# BLE_test.net
KiCad netlist of a schematic drawn in EAGLE
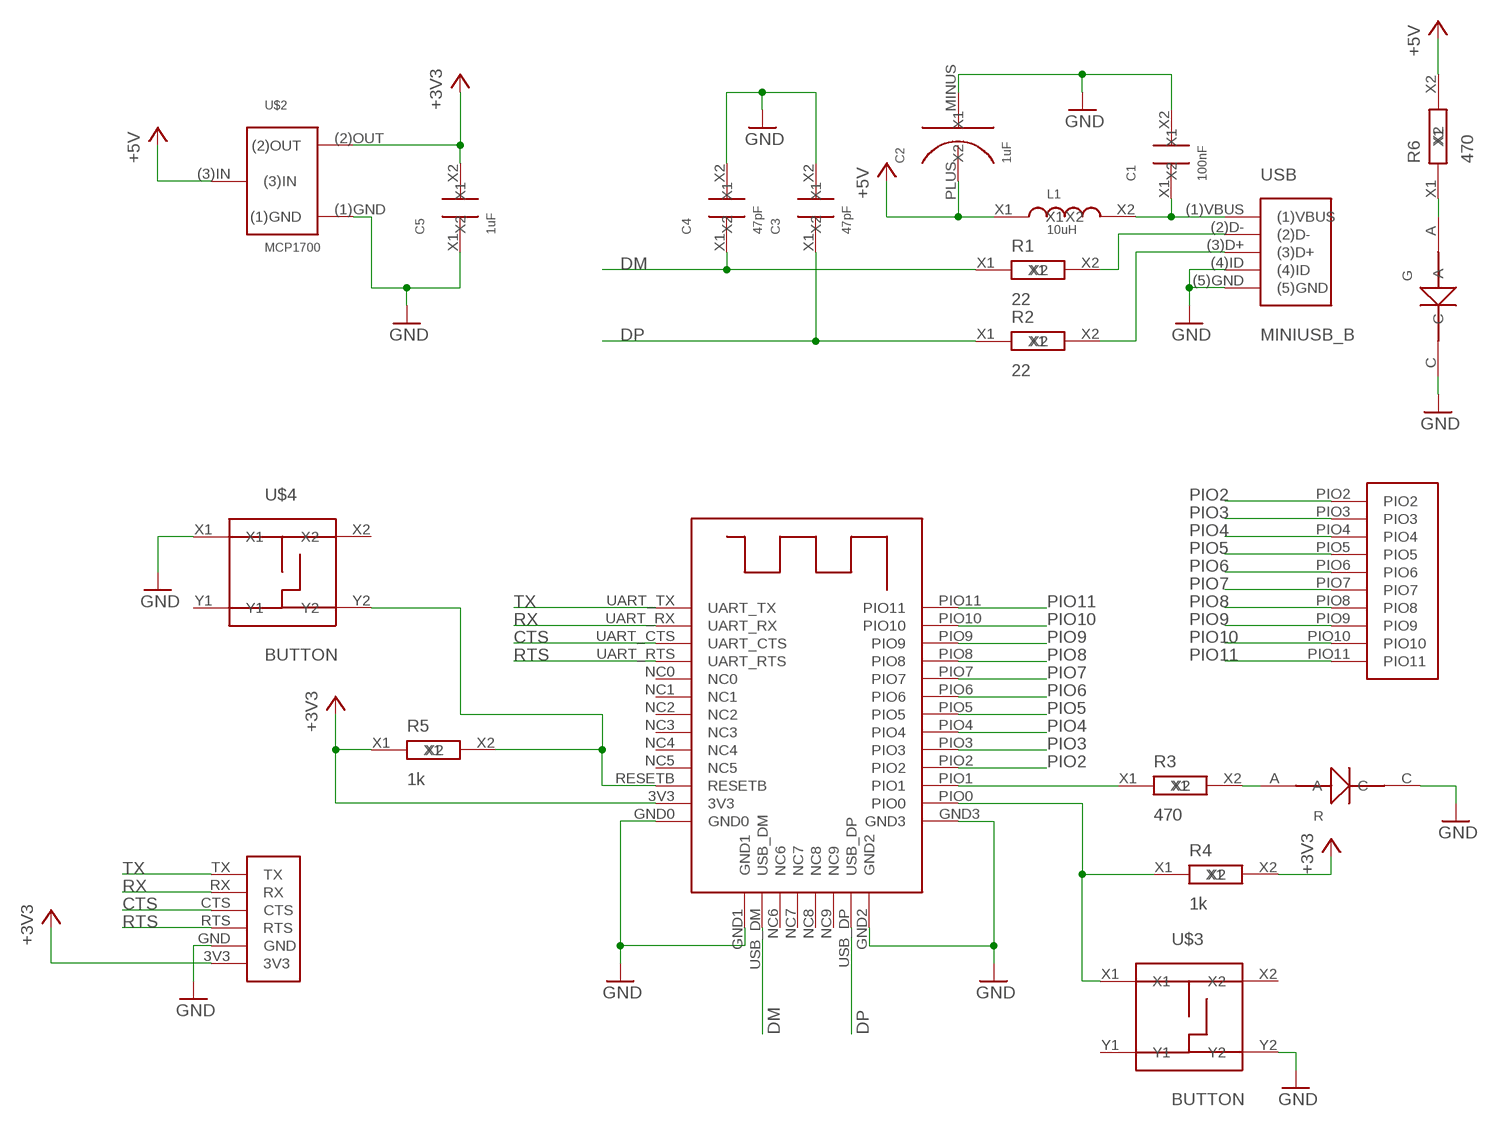
[diagram p0: schematic, sheet 1]

(export (version "E")
  (design (tool "Eeschema 10.0.6"))
  (components
    (comp (ref "C1")
      (value "100nF")
      (footprint "eagle-import:SMD_2.1X1.25")
      (libsource (lib "eagle-import") (part "C_SMD_2.1X1.25"))
    )
    (comp (ref "C2")
      (value "1uF")
      (footprint "eagle-import:C_SMD_TA_A")
      (libsource (lib "eagle-import") (part "C_SMD_TA_A"))
    )
    (comp (ref "C3")
      (value "47pF")
      (footprint "eagle-import:SMD_2.1X1.25")
      (libsource (lib "eagle-import") (part "C_SMD_2.1X1.25"))
    )
    (comp (ref "C4")
      (value "47pF")
      (footprint "eagle-import:SMD_2.1X1.25")
      (libsource (lib "eagle-import") (part "C_SMD_2.1X1.25"))
    )
    (comp (ref "C5")
      (value "1uF")
      (footprint "eagle-import:SMD_2.1X1.25")
      (libsource (lib "eagle-import") (part "C_SMD_2.1X1.25"))
    )
    (comp (ref "G")
      (value "LED0805")
      (footprint "eagle-import:SMD0805")
      (libsource (lib "eagle-import") (part "LED0805"))
    )
    (comp (ref "L1")
      (value "10uH")
      (footprint "eagle-import:SMD_2.1X1.25")
      (libsource (lib "eagle-import") (part "L_SMD_2.1X1.25"))
    )
    (comp (ref "R")
      (value "LED0805")
      (footprint "eagle-import:SMD0805")
      (libsource (lib "eagle-import") (part "LED0805"))
    )
    (comp (ref "R1")
      (value "22")
      (footprint "eagle-import:SMD_2.1X1.25")
      (libsource (lib "eagle-import") (part "R_SMD_2.1X1.25"))
    )
    (comp (ref "R2")
      (value "22")
      (footprint "eagle-import:SMD_2.1X1.25")
      (libsource (lib "eagle-import") (part "R_SMD_2.1X1.25"))
    )
    (comp (ref "R3")
      (value "470")
      (footprint "eagle-import:SMD_2.1X1.25")
      (libsource (lib "eagle-import") (part "R_SMD_2.1X1.25"))
    )
    (comp (ref "R4")
      (value "1k")
      (footprint "eagle-import:SMD_2.1X1.25")
      (libsource (lib "eagle-import") (part "R_SMD_2.1X1.25"))
    )
    (comp (ref "R5")
      (value "1k")
      (footprint "eagle-import:SMD_2.1X1.25")
      (libsource (lib "eagle-import") (part "R_SMD_2.1X1.25"))
    )
    (comp (ref "R6")
      (value "470")
      (footprint "eagle-import:SMD_2.1X1.25")
      (libsource (lib "eagle-import") (part "R_SMD_2.1X1.25"))
    )
    (comp (ref "U$1")
      (value "BLE_HM10")
      (footprint "eagle-import:BLE_HM10")
      (libsource (lib "eagle-import") (part "BLE_HM10"))
    )
    (comp (ref "U$2")
      (value "MCP1700")
      (footprint "eagle-import:MCP1700")
      (libsource (lib "eagle-import") (part "MCP1700"))
    )
    (comp (ref "U$3")
      (value "BUTTON")
      (footprint "eagle-import:BUTTON")
      (libsource (lib "eagle-import") (part "BUTTON"))
    )
    (comp (ref "U$4")
      (value "BUTTON")
      (footprint "eagle-import:BUTTON")
      (libsource (lib "eagle-import") (part "BUTTON"))
    )
    (comp (ref "U$5")
      (value "PIN6")
      (footprint "eagle-import:PIN6")
      (libsource (lib "eagle-import") (part "PIN6"))
    )
    (comp (ref "U$7")
      (value "PIO_10")
      (footprint "eagle-import:PIO_10")
      (libsource (lib "eagle-import") (part "PIO_10"))
    )
    (comp (ref "USB")
      (value "MINIUSB_B")
      (footprint "eagle-import:MINIUSB_B")
      (libsource (lib "eagle-import") (part "MINIUSB_B"))
    )
  )
  (nets
    (net (code "1") (name "+3V3") (class "Default")
      (node (ref "C5") (pin "X2") (pinfunction "X2_X2") (pintype "bidirectional"))
      (node (ref "R4") (pin "X2") (pinfunction "X2_X2") (pintype "bidirectional"))
      (node (ref "R5") (pin "X1") (pinfunction "X1_X1") (pintype "bidirectional"))
      (node (ref "U$1") (pin "3V3") (pinfunction "3V3_3V3") (pintype "bidirectional"))
      (node (ref "U$2") (pin "(2)OUT") (pinfunction "(2)OUT_(2)OUT") (pintype "bidirectional"))
      (node (ref "U$5") (pin "3V3") (pinfunction "3V3_3V3") (pintype "bidirectional"))
    )
    (net (code "2") (name "+5V") (class "Default")
      (node (ref "C2") (pin "PLUS") (pinfunction "X1_PLUS") (pintype "bidirectional"))
      (node (ref "L1") (pin "X1") (pinfunction "X1_X1") (pintype "bidirectional"))
      (node (ref "R6") (pin "X2") (pinfunction "X2_X2") (pintype "bidirectional"))
      (node (ref "U$2") (pin "(3)IN") (pinfunction "(3)IN_(3)IN") (pintype "bidirectional"))
    )
    (net (code "3") (name "/CTS") (class "Default")
      (node (ref "U$1") (pin "UART_CTS") (pinfunction "UART_CTS_UART_CTS") (pintype "bidirectional"))
      (node (ref "U$5") (pin "CTS") (pinfunction "CTS_CTS") (pintype "bidirectional"))
    )
    (net (code "4") (name "/DM") (class "Default")
      (node (ref "C4") (pin "X1") (pinfunction "X1_X1") (pintype "bidirectional"))
      (node (ref "R1") (pin "X1") (pinfunction "X1_X1") (pintype "bidirectional"))
      (node (ref "U$1") (pin "USB_DM") (pinfunction "USB_DM_USB_DM") (pintype "bidirectional"))
    )
    (net (code "5") (name "/DP") (class "Default")
      (node (ref "C3") (pin "X1") (pinfunction "X1_X1") (pintype "bidirectional"))
      (node (ref "R2") (pin "X1") (pinfunction "X1_X1") (pintype "bidirectional"))
      (node (ref "U$1") (pin "USB_DP") (pinfunction "USB_DP_USB_DP") (pintype "bidirectional"))
    )
    (net (code "6") (name "/PIO2") (class "Default")
      (node (ref "U$1") (pin "PIO2") (pinfunction "PIO2_PIO2") (pintype "bidirectional"))
      (node (ref "U$7") (pin "PIO2") (pinfunction "PIO2_PIO2") (pintype "bidirectional"))
    )
    (net (code "7") (name "/PIO3") (class "Default")
      (node (ref "U$1") (pin "PIO3") (pinfunction "PIO3_PIO3") (pintype "bidirectional"))
      (node (ref "U$7") (pin "PIO3") (pinfunction "PIO3_PIO3") (pintype "bidirectional"))
    )
    (net (code "8") (name "/PIO4") (class "Default")
      (node (ref "U$1") (pin "PIO4") (pinfunction "PIO4_PIO4") (pintype "bidirectional"))
      (node (ref "U$7") (pin "PIO4") (pinfunction "PIO4_PIO4") (pintype "bidirectional"))
    )
    (net (code "9") (name "/PIO5") (class "Default")
      (node (ref "U$1") (pin "PIO5") (pinfunction "PIO5_PIO5") (pintype "bidirectional"))
      (node (ref "U$7") (pin "PIO5") (pinfunction "PIO5_PIO5") (pintype "bidirectional"))
    )
    (net (code "10") (name "/PIO6") (class "Default")
      (node (ref "U$1") (pin "PIO6") (pinfunction "PIO6_PIO6") (pintype "bidirectional"))
      (node (ref "U$7") (pin "PIO6") (pinfunction "PIO6_PIO6") (pintype "bidirectional"))
    )
    (net (code "11") (name "/PIO7") (class "Default")
      (node (ref "U$1") (pin "PIO7") (pinfunction "PIO7_PIO7") (pintype "bidirectional"))
      (node (ref "U$7") (pin "PIO7") (pinfunction "PIO7_PIO7") (pintype "bidirectional"))
    )
    (net (code "12") (name "/PIO8") (class "Default")
      (node (ref "U$1") (pin "PIO8") (pinfunction "PIO8_PIO8") (pintype "bidirectional"))
      (node (ref "U$7") (pin "PIO8") (pinfunction "PIO8_PIO8") (pintype "bidirectional"))
    )
    (net (code "13") (name "/PIO9") (class "Default")
      (node (ref "U$1") (pin "PIO9") (pinfunction "PIO9_PIO9") (pintype "bidirectional"))
      (node (ref "U$7") (pin "PIO9") (pinfunction "PIO9_PIO9") (pintype "bidirectional"))
    )
    (net (code "14") (name "/PIO10") (class "Default")
      (node (ref "U$1") (pin "PIO10") (pinfunction "PIO10_PIO10") (pintype "bidirectional"))
      (node (ref "U$7") (pin "PIO10") (pinfunction "PIO10_PIO10") (pintype "bidirectional"))
    )
    (net (code "15") (name "/PIO11") (class "Default")
      (node (ref "U$1") (pin "PIO11") (pinfunction "PIO11_PIO11") (pintype "bidirectional"))
      (node (ref "U$7") (pin "PIO11") (pinfunction "PIO11_PIO11") (pintype "bidirectional"))
    )
    (net (code "16") (name "/RTS") (class "Default")
      (node (ref "U$1") (pin "UART_RTS") (pinfunction "UART_RTS_UART_RTS") (pintype "bidirectional"))
      (node (ref "U$5") (pin "RTS") (pinfunction "RTS_RTS") (pintype "bidirectional"))
    )
    (net (code "17") (name "/RX") (class "Default")
      (node (ref "U$1") (pin "UART_RX") (pinfunction "UART_RX_UART_RX") (pintype "bidirectional"))
      (node (ref "U$5") (pin "RX") (pinfunction "RX_RX") (pintype "bidirectional"))
    )
    (net (code "18") (name "/TX") (class "Default")
      (node (ref "U$1") (pin "UART_TX") (pinfunction "UART_TX_UART_TX") (pintype "bidirectional"))
      (node (ref "U$5") (pin "TX") (pinfunction "TX_TX") (pintype "bidirectional"))
    )
    (net (code "19") (name "GND") (class "Default")
      (node (ref "C1") (pin "X2") (pinfunction "X2_X2") (pintype "bidirectional"))
      (node (ref "C2") (pin "MINUS") (pinfunction "X2_MINUS") (pintype "bidirectional"))
      (node (ref "C3") (pin "X2") (pinfunction "X2_X2") (pintype "bidirectional"))
      (node (ref "C4") (pin "X2") (pinfunction "X2_X2") (pintype "bidirectional"))
      (node (ref "C5") (pin "X1") (pinfunction "X1_X1") (pintype "bidirectional"))
      (node (ref "G") (pin "C") (pinfunction "C_C") (pintype "bidirectional"))
      (node (ref "R") (pin "C") (pinfunction "C_C") (pintype "bidirectional"))
      (node (ref "U$1") (pin "GND0") (pinfunction "GND0_GND0") (pintype "bidirectional"))
      (node (ref "U$1") (pin "GND1") (pinfunction "GND1_GND1") (pintype "bidirectional"))
      (node (ref "U$1") (pin "GND2") (pinfunction "GND2_GND2") (pintype "bidirectional"))
      (node (ref "U$1") (pin "GND3") (pinfunction "GND3_GND3") (pintype "bidirectional"))
      (node (ref "U$2") (pin "(1)GND") (pinfunction "(1)GND_(1)GND") (pintype "bidirectional"))
      (node (ref "U$3") (pin "Y2") (pinfunction "Y2_Y2") (pintype "bidirectional"))
      (node (ref "U$4") (pin "X1") (pinfunction "X1_X1") (pintype "bidirectional"))
      (node (ref "U$5") (pin "GND") (pinfunction "GND_GND") (pintype "bidirectional"))
      (node (ref "USB") (pin "(4)ID") (pinfunction "(4)ID_(4)ID") (pintype "bidirectional"))
      (node (ref "USB") (pin "(5)GND") (pinfunction "(5)GND_(5)GND") (pintype "bidirectional"))
    )
    (net (code "20") (name "Net-(C1-PadX1)") (class "Default")
      (node (ref "C1") (pin "X1") (pinfunction "X1_X1") (pintype "bidirectional"))
      (node (ref "L1") (pin "X2") (pinfunction "X2_X2") (pintype "bidirectional"))
      (node (ref "USB") (pin "(1)VBUS") (pinfunction "(1)VBUS_(1)VBUS") (pintype "bidirectional"))
    )
    (net (code "21") (name "Net-(G-PadA)") (class "Default")
      (node (ref "G") (pin "A") (pinfunction "A_A") (pintype "bidirectional"))
      (node (ref "R6") (pin "X1") (pinfunction "X1_X1") (pintype "bidirectional"))
    )
    (net (code "22") (name "Net-(R-PadA)") (class "Default")
      (node (ref "R") (pin "A") (pinfunction "A_A") (pintype "bidirectional"))
      (node (ref "R3") (pin "X2") (pinfunction "X2_X2") (pintype "bidirectional"))
    )
    (net (code "23") (name "Net-(R1-PadX2)") (class "Default")
      (node (ref "R1") (pin "X2") (pinfunction "X2_X2") (pintype "bidirectional"))
      (node (ref "USB") (pin "(2)D-") (pinfunction "(2)D-_(2)D-") (pintype "bidirectional"))
    )
    (net (code "24") (name "Net-(R2-PadX2)") (class "Default")
      (node (ref "R2") (pin "X2") (pinfunction "X2_X2") (pintype "bidirectional"))
      (node (ref "USB") (pin "(3)D+") (pinfunction "(3)D+_(3)D+") (pintype "bidirectional"))
    )
    (net (code "25") (name "Net-(R3-PadX1)") (class "Default")
      (node (ref "R3") (pin "X1") (pinfunction "X1_X1") (pintype "bidirectional"))
      (node (ref "U$1") (pin "PIO1") (pinfunction "PIO1_PIO1") (pintype "bidirectional"))
    )
    (net (code "26") (name "Net-(R4-PadX1)") (class "Default")
      (node (ref "R4") (pin "X1") (pinfunction "X1_X1") (pintype "bidirectional"))
      (node (ref "U$1") (pin "PIO0") (pinfunction "PIO0_PIO0") (pintype "bidirectional"))
      (node (ref "U$3") (pin "X1") (pinfunction "X1_X1") (pintype "bidirectional"))
    )
    (net (code "27") (name "Net-(R5-PadX2)") (class "Default")
      (node (ref "R5") (pin "X2") (pinfunction "X2_X2") (pintype "bidirectional"))
      (node (ref "U$1") (pin "RESETB") (pinfunction "RESETB_RESETB") (pintype "bidirectional"))
      (node (ref "U$4") (pin "Y2") (pinfunction "Y2_Y2") (pintype "bidirectional"))
    )
    (net (code "28") (name "unconnected-(U$1-PadNC0)") (class "Default")
      (node (ref "U$1") (pin "NC0") (pinfunction "NC0_NC0") (pintype "bidirectional"))
    )
    (net (code "29") (name "unconnected-(U$1-PadNC1)") (class "Default")
      (node (ref "U$1") (pin "NC1") (pinfunction "NC1_NC1") (pintype "bidirectional"))
    )
    (net (code "30") (name "unconnected-(U$1-PadNC2)") (class "Default")
      (node (ref "U$1") (pin "NC2") (pinfunction "NC2_NC2") (pintype "bidirectional"))
    )
    (net (code "31") (name "unconnected-(U$1-PadNC3)") (class "Default")
      (node (ref "U$1") (pin "NC3") (pinfunction "NC3_NC3") (pintype "bidirectional"))
    )
    (net (code "32") (name "unconnected-(U$1-PadNC4)") (class "Default")
      (node (ref "U$1") (pin "NC4") (pinfunction "NC4_NC4") (pintype "bidirectional"))
    )
    (net (code "33") (name "unconnected-(U$1-PadNC5)") (class "Default")
      (node (ref "U$1") (pin "NC5") (pinfunction "NC5_NC5") (pintype "bidirectional"))
    )
    (net (code "34") (name "unconnected-(U$1-PadNC6)") (class "Default")
      (node (ref "U$1") (pin "NC6") (pinfunction "NC6_NC6") (pintype "bidirectional"))
    )
    (net (code "35") (name "unconnected-(U$1-PadNC7)") (class "Default")
      (node (ref "U$1") (pin "NC7") (pinfunction "NC7_NC7") (pintype "bidirectional"))
    )
    (net (code "36") (name "unconnected-(U$1-PadNC8)") (class "Default")
      (node (ref "U$1") (pin "NC8") (pinfunction "NC8_NC8") (pintype "bidirectional"))
    )
    (net (code "37") (name "unconnected-(U$1-PadNC9)") (class "Default")
      (node (ref "U$1") (pin "NC9") (pinfunction "NC9_NC9") (pintype "bidirectional"))
    )
    (net (code "38") (name "unconnected-(U$3-PadX2)") (class "Default")
      (node (ref "U$3") (pin "X2") (pinfunction "X2_X2") (pintype "bidirectional"))
    )
    (net (code "39") (name "unconnected-(U$3-PadY1)") (class "Default")
      (node (ref "U$3") (pin "Y1") (pinfunction "Y1_Y1") (pintype "bidirectional"))
    )
    (net (code "40") (name "unconnected-(U$4-PadX2)") (class "Default")
      (node (ref "U$4") (pin "X2") (pinfunction "X2_X2") (pintype "bidirectional"))
    )
    (net (code "41") (name "unconnected-(U$4-PadY1)") (class "Default")
      (node (ref "U$4") (pin "Y1") (pinfunction "Y1_Y1") (pintype "bidirectional"))
    )
  )
)
